# ESC.net
KiCad netlist of a schematic drawn in Altium Designer
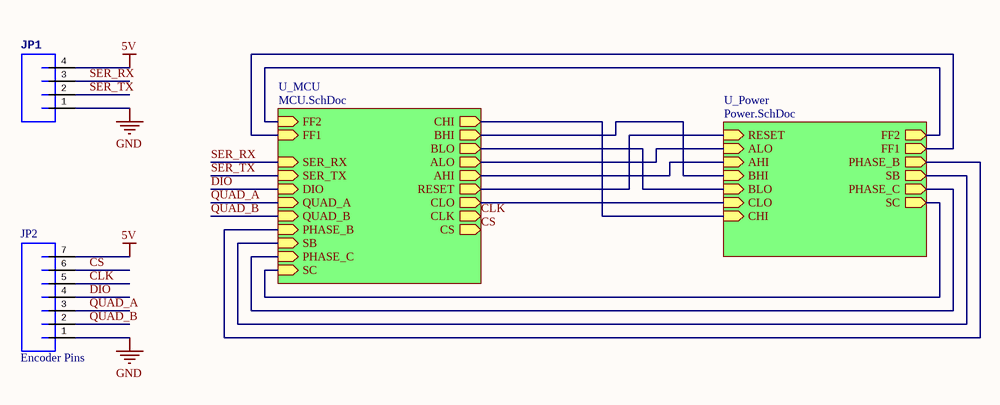
[diagram p0: ESC.SchDoc]

(export (version "E")
  (design (tool "Eeschema 10.0.6"))
  (components
    (comp (ref "JP1")
      (value "~")
      (footprint "JST-4-PTH-VERT")
      (libsource (lib "Components") (part "JST_4_VERT"))
    )
    (comp (ref "JP2")
      (value "Encoder Pins")
      (footprint "JST-7-PTH-VERT")
      (libsource (lib "Components") (part "JST_7_VERT"))
    )
  )
  (nets
    (net (code "6") (name "/CLK") (class "Default")
      (node (ref "JP2") (pin "5") (pinfunction "5_5") (pintype "passive"))
    )
    (net (code "8") (name "/CS") (class "Default")
      (node (ref "JP2") (pin "6") (pinfunction "6_6") (pintype "passive"))
    )
    (net (code "9") (name "/DIO") (class "Default")
      (node (ref "JP2") (pin "4") (pinfunction "4_4") (pintype "passive"))
    )
    (net (code "14") (name "/QUAD_A") (class "Default")
      (node (ref "JP2") (pin "3") (pinfunction "3_3") (pintype "passive"))
    )
    (net (code "15") (name "/QUAD_B") (class "Default")
      (node (ref "JP2") (pin "2") (pinfunction "2_2") (pintype "passive"))
    )
    (net (code "19") (name "/SER_RX") (class "Default")
      (node (ref "JP1") (pin "3") (pinfunction "3_3") (pintype "passive"))
    )
    (net (code "20") (name "/SER_TX") (class "Default")
      (node (ref "JP1") (pin "2") (pinfunction "2_2") (pintype "passive"))
    )
    (net (code "21") (name "5V") (class "Default")
      (node (ref "JP1") (pin "4") (pinfunction "4_4") (pintype "passive"))
      (node (ref "JP2") (pin "7") (pinfunction "7_7") (pintype "passive"))
    )
    (net (code "22") (name "GND") (class "Default")
      (node (ref "JP1") (pin "1") (pinfunction "1_1") (pintype "passive"))
      (node (ref "JP2") (pin "1") (pinfunction "1_1") (pintype "passive"))
    )
  )
)
